# MK2B.net
KiCad netlist of a schematic drawn in Altium Designer
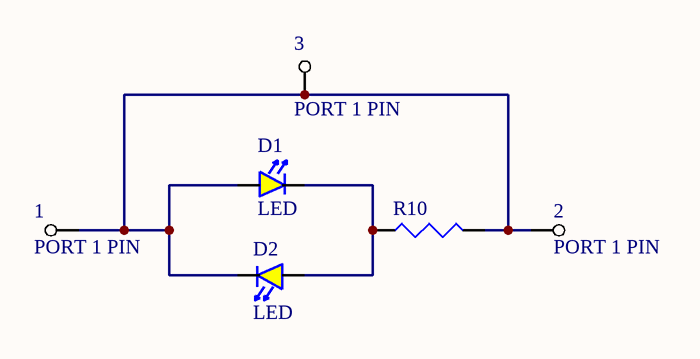
[diagram p0: MK2B.SchDoc]

(export (version "E")
  (design (tool "Eeschema 10.0.6"))
  (components
    (comp (ref "1")
      (value "PORT 1 PIN")
      (footprint "PIN1 4mm hole 2")
      (libsource (lib "gc") (part "PORT 1 PIN"))
    )
    (comp (ref "2")
      (value "PORT 1 PIN")
      (footprint "PIN1 4mm hole 2")
      (libsource (lib "gc") (part "PORT 1 PIN"))
    )
    (comp (ref "3")
      (value "PORT 1 PIN")
      (footprint "PIN1 4mm hole 2")
      (libsource (lib "gc") (part "PORT 1 PIN"))
    )
    (comp (ref "D1")
      (value "LED")
      (footprint "Res 2012-0805")
      (description "Hyper-Bright Low Current LED OSRAM")
      (libsource (lib "gc") (part "LED SMD OSRAM 0603"))
    )
    (comp (ref "D2")
      (value "LED")
      (footprint "Res 2012-0805")
      (description "Hyper-Bright Low Current LED OSRAM")
      (libsource (lib "gc") (part "LED SMD OSRAM 0603"))
    )
    (comp (ref "R10")
      (value "Res3")
      (footprint "Res 2012-0805")
      (description "Resistor")
      (fields (field (name "PUBLISHER") "Altium Limited"))
      (libsource (lib "gc") (part "Res3"))
    )
  )
  (nets
    (net (code "1") (name "Net-(D1-A)") (class "Default")
      (node (ref "1") (pin "1") (pinfunction "1_1") (pintype "passive"))
      (node (ref "2") (pin "1") (pinfunction "1_1") (pintype "passive"))
      (node (ref "3") (pin "1") (pinfunction "1_1") (pintype "passive"))
      (node (ref "D1") (pin "1") (pinfunction "A_1") (pintype "passive"))
      (node (ref "D2") (pin "2") (pinfunction "K_2") (pintype "passive"))
      (node (ref "R10") (pin "2") (pinfunction "2_2") (pintype "passive"))
    )
    (net (code "2") (name "Net-(D1-K)") (class "Default")
      (node (ref "D1") (pin "2") (pinfunction "K_2") (pintype "passive"))
      (node (ref "D2") (pin "1") (pinfunction "A_1") (pintype "passive"))
      (node (ref "R10") (pin "1") (pinfunction "1_1") (pintype "passive"))
    )
  )
)
